# Power_Regulators_RF_3.net
KiCad netlist of a schematic drawn in Altium Designer
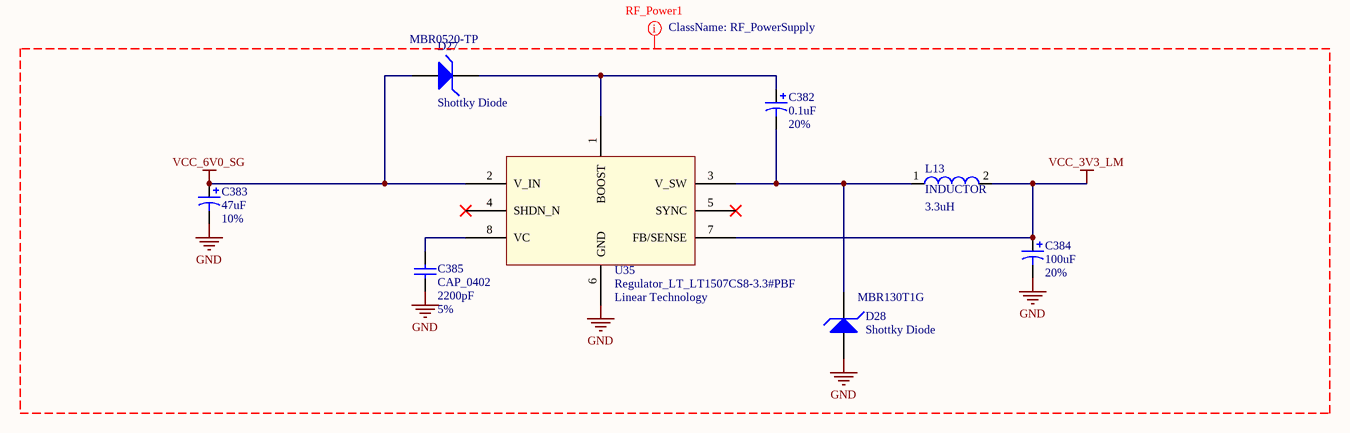
[diagram p0: Power_Regulators_RF_3.SchDoc]

(export (version "E")
  (design (tool "Eeschema 10.0.6"))
  (components
    (comp (ref "C382")
      (value "0.1uF")
      (footprint "Polarized_CAPC1206(3216)")
      (description "CAP TANT 0.1UF 35V 20% 1206")
      (fields
        (field (name "TOLERANCE") "20%")
        (field (name "PART NUMBER") "T491A104M035AT")
        (field (name "MANUFACTURER") "Kemet")
      )
      (libsource (lib "COMRAD_Database") (part "Cap Pol1"))
    )
    (comp (ref "C383")
      (value "47uF")
      (footprint "Polarized_CAPC1210(3225)")
      (description "CAP TANT 47UF 16V 10% 1210")
      (fields
        (field (name "TOLERANCE") "10%")
        (field (name "PART NUMBER") "F951C476KBAAQ2")
        (field (name "MANUFACTURER") "Nichicon")
      )
      (libsource (lib "COMRAD_Database") (part "Cap Pol1"))
    )
    (comp (ref "C384")
      (value "100uF")
      (footprint "Polarized_CAPC1210(3225)")
      (description "100uF, tantalum, 20% 10V, 1210")
      (fields
        (field (name "TOLERANCE") "20%")
        (field (name "PART NUMBER") "TLCT107M010XTA")
        (field (name "MANUFACTURER") "AVX Corporation")
      )
      (libsource (lib "COMRAD_Database") (part "Cap Pol1"))
    )
    (comp (ref "C385")
      (value "CAP_0402")
      (footprint "CAPC0402(1005)60_N")
      (description "CAP CER 2200PF 10V 5% SL 0402")
      (fields
        (field (name "ALTIUM_VALUE") "2200pF")
        (field (name "TOLERANCE") "5%")
        (field (name "PART NUMBER") "C1005SL1A222J")
        (field (name "MANUFACTURER") "TDK Corporation")
      )
      (libsource (lib "COMRAD_Database") (part "CAP_0402"))
    )
    (comp (ref "D27")
      (value "Shottky Diode")
      (footprint "SchottkyDiode_MBR0520-TP_SOD-123")
      (description "DIODE SCHOTTKY 20V 500MA SOD123")
      (fields (field (name "PART NUMBER") "MBR0520-TP") (field (name "MANUFACTURER") "Micro Commercial Co"))
      (libsource (lib "COMRAD_Database") (part "ShottkyDiode"))
    )
    (comp (ref "D28")
      (value "Shottky Diode")
      (footprint "SchottkyDiode_MBR130T1G_SOD-123")
      (description "DIODE SCHOTTKY 30V 1A SOD123")
      (fields (field (name "PART NUMBER") "MBR130T1G") (field (name "MANUFACTURER") "ON Semiconductor"))
      (libsource (lib "COMRAD_Database") (part "ShottkyDiode"))
    )
    (comp (ref "L13")
      (value "INDUCTOR")
      (footprint "Inductor_IHSM4825ER_2-PIN")
      (description "INDUCTOR POWER 3.3UH 4.6A SMD")
      (fields
        (field (name "ALTIUM_VALUE") "3.3uH")
        (field (name "PART NUMBER") "IHSM4825ER3R3L")
        (field (name "MANUFACTURER") "Vishay Dale")
      )
      (libsource (lib "COMRAD_Database") (part "SYM-0029-00001-1"))
    )
    (comp (ref "U35")
      (value "Regulator_LT_LT1507CS8-3.3#PBF")
      (footprint "Regulator_LT_LT1507CS8-3.3#PBF_8SOIC")
      (description "IC REG BUCK 3.3V 1.5A 8SOIC")
      (fields
        (field (name "PART NUMBER") "LT1507CS8-3.3#PBF")
        (field (name "MANUFACTURER") "Linear Technology")
      )
      (libsource (lib "COMRAD_Database") (part "Regulator_LT_LT1507CS8-3.3#PBF"))
    )
  )
  (nets
    (net (code "1") (name "GND") (class "Default")
      (node (ref "C383") (pin "2") (pinfunction "2_2") (pintype "passive"))
      (node (ref "C384") (pin "2") (pinfunction "2_2") (pintype "passive"))
      (node (ref "C385") (pin "1") (pinfunction "1_1") (pintype "passive"))
      (node (ref "D28") (pin "2") (pinfunction "A_2") (pintype "passive"))
      (node (ref "U35") (pin "6") (pinfunction "GND_6") (pintype "power_in"))
    )
    (net (code "2") (name "Net-(D27-K)") (class "Default")
      (node (ref "C382") (pin "1") (pinfunction "1_1") (pintype "passive"))
      (node (ref "D27") (pin "1") (pinfunction "K_1") (pintype "passive"))
      (node (ref "U35") (pin "1") (pinfunction "BOOST_1") (pintype "passive"))
    )
    (net (code "3") (name "Net-(D28-K)") (class "Default")
      (node (ref "C382") (pin "2") (pinfunction "2_2") (pintype "passive"))
      (node (ref "D28") (pin "1") (pinfunction "K_1") (pintype "passive"))
      (node (ref "L13") (pin "1") (pinfunction "1_1") (pintype "passive"))
      (node (ref "U35") (pin "3") (pinfunction "V_SW_3") (pintype "power_in"))
    )
    (net (code "4") (name "Net-(U35-VC)") (class "Default")
      (node (ref "C385") (pin "2") (pinfunction "2_2") (pintype "passive"))
      (node (ref "U35") (pin "8") (pinfunction "VC_8") (pintype "passive"))
    )
    (net (code "5") (name "VCC_3V3_LM") (class "Default")
      (node (ref "C384") (pin "1") (pinfunction "1_1") (pintype "passive"))
      (node (ref "L13") (pin "2") (pinfunction "2_2") (pintype "passive"))
      (node (ref "U35") (pin "7") (pinfunction "FB/SENSE_7") (pintype "power_in"))
    )
    (net (code "6") (name "VCC_6V0_SG") (class "Default")
      (node (ref "C383") (pin "1") (pinfunction "1_1") (pintype "passive"))
      (node (ref "D27") (pin "2") (pinfunction "A_2") (pintype "passive"))
      (node (ref "U35") (pin "2") (pinfunction "V_IN_2") (pintype "power_in"))
    )
    (net (code "7") (name "unconnected-(U35-SHDN_N-Pad4)") (class "Default")
      (node (ref "U35") (pin "4") (pinfunction "SHDN_N_4") (pintype "passive+no_connect"))
    )
    (net (code "8") (name "unconnected-(U35-SYNC-Pad5)") (class "Default")
      (node (ref "U35") (pin "5") (pinfunction "SYNC_5") (pintype "passive+no_connect"))
    )
  )
)
